# TTL_TO_RS485.net
KiCad netlist of a schematic drawn in Altium Designer
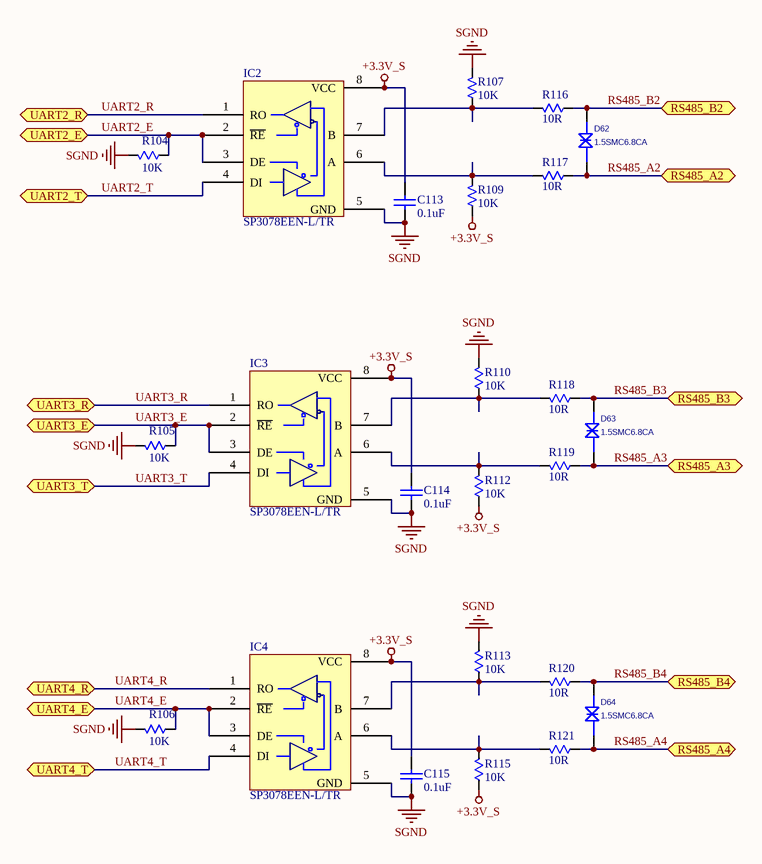
[diagram p0: TTL_TO_RS485.SchDoc]

(export (version "E")
  (design (tool "Eeschema 10.0.6"))
  (components
    (comp (ref "C113")
      (value "0.1uF")
      (footprint "C0805")
      (description "CAP")
      (fields (field (name "PUBLISHER") "Altium Limited"))
      (libsource (lib "Passive Components Class") (part "CAP"))
    )
    (comp (ref "C114")
      (value "0.1uF")
      (footprint "C0805")
      (description "CAP")
      (fields (field (name "PUBLISHER") "Altium Limited"))
      (libsource (lib "Passive Components Class") (part "CAP"))
    )
    (comp (ref "C115")
      (value "0.1uF")
      (footprint "C0805")
      (description "CAP")
      (fields (field (name "PUBLISHER") "Altium Limited"))
      (libsource (lib "Passive Components Class") (part "CAP"))
    )
    (comp (ref "D62")
      (value "1.5SMC6.8CA")
      (footprint "SMB")
      (fields (field (name "MANUFACTURER") "SemiTel"))
      (libsource (lib "*") (part "P0080_1"))
    )
    (comp (ref "D63")
      (value "1.5SMC6.8CA")
      (footprint "SMB")
      (fields (field (name "MANUFACTURER") "SemiTel"))
      (libsource (lib "*") (part "P0080_1"))
    )
    (comp (ref "D64")
      (value "1.5SMC6.8CA")
      (footprint "SMB")
      (fields (field (name "MANUFACTURER") "SemiTel"))
      (libsource (lib "*") (part "P0080_1"))
    )
    (comp (ref "IC2")
      (value "SP3078EEN-L/TR")
      (footprint "SO-8")
      (libsource (lib "Interface Class") (part "SP3078EEN"))
    )
    (comp (ref "IC3")
      (value "SP3078EEN-L/TR")
      (footprint "SO-8")
      (libsource (lib "Interface Class") (part "SP3078EEN"))
    )
    (comp (ref "IC4")
      (value "SP3078EEN-L/TR")
      (footprint "SO-8")
      (libsource (lib "Interface Class") (part "SP3078EEN"))
    )
    (comp (ref "R104")
      (value "10K")
      (footprint "R0805")
      (description "Resistor")
      (fields (field (name "PUBLISHER") "Altium Limited"))
      (libsource (lib "Passive Components Class") (part "RES"))
    )
    (comp (ref "R105")
      (value "10K")
      (footprint "R0805")
      (description "Resistor")
      (fields (field (name "PUBLISHER") "Altium Limited"))
      (libsource (lib "Passive Components Class") (part "RES"))
    )
    (comp (ref "R106")
      (value "10K")
      (footprint "R0805")
      (description "Resistor")
      (fields (field (name "PUBLISHER") "Altium Limited"))
      (libsource (lib "Passive Components Class") (part "RES"))
    )
    (comp (ref "R107")
      (value "10K")
      (footprint "R0805")
      (description "Resistor")
      (fields (field (name "PUBLISHER") "Altium Limited"))
      (libsource (lib "") (part "RES_1"))
    )
    (comp (ref "R109")
      (value "10K")
      (footprint "R0805")
      (description "Resistor")
      (fields (field (name "PUBLISHER") "Altium Limited"))
      (libsource (lib "") (part "RES_1"))
    )
    (comp (ref "R110")
      (value "10K")
      (footprint "R0805")
      (description "Resistor")
      (fields (field (name "PUBLISHER") "Altium Limited"))
      (libsource (lib "") (part "RES_1"))
    )
    (comp (ref "R112")
      (value "10K")
      (footprint "R0805")
      (description "Resistor")
      (fields (field (name "PUBLISHER") "Altium Limited"))
      (libsource (lib "") (part "RES_1"))
    )
    (comp (ref "R113")
      (value "10K")
      (footprint "R0805")
      (description "Resistor")
      (fields (field (name "PUBLISHER") "Altium Limited"))
      (libsource (lib "") (part "RES_1"))
    )
    (comp (ref "R115")
      (value "10K")
      (footprint "R0805")
      (description "Resistor")
      (fields (field (name "PUBLISHER") "Altium Limited"))
      (libsource (lib "") (part "RES_1"))
    )
    (comp (ref "R116")
      (value "10R")
      (footprint "R0805")
      (description "Resistor")
      (fields (field (name "PUBLISHER") "Altium Limited"))
      (libsource (lib "Passive Components Class") (part "RES"))
    )
    (comp (ref "R117")
      (value "10R")
      (footprint "R0805")
      (description "Resistor")
      (fields (field (name "PUBLISHER") "Altium Limited"))
      (libsource (lib "Passive Components Class") (part "RES"))
    )
    (comp (ref "R118")
      (value "10R")
      (footprint "R0805")
      (description "Resistor")
      (fields (field (name "PUBLISHER") "Altium Limited"))
      (libsource (lib "Passive Components Class") (part "RES"))
    )
    (comp (ref "R119")
      (value "10R")
      (footprint "R0805")
      (description "Resistor")
      (fields (field (name "PUBLISHER") "Altium Limited"))
      (libsource (lib "Passive Components Class") (part "RES"))
    )
    (comp (ref "R120")
      (value "10R")
      (footprint "R0805")
      (description "Resistor")
      (fields (field (name "PUBLISHER") "Altium Limited"))
      (libsource (lib "Passive Components Class") (part "RES"))
    )
    (comp (ref "R121")
      (value "10R")
      (footprint "R0805")
      (description "Resistor")
      (fields (field (name "PUBLISHER") "Altium Limited"))
      (libsource (lib "Passive Components Class") (part "RES"))
    )
  )
  (nets
    (net (code "1") (name "+3.3V_S") (class "Default")
      (node (ref "C113") (pin "2") (pinfunction "2_2") (pintype "passive"))
      (node (ref "C114") (pin "2") (pinfunction "2_2") (pintype "passive"))
      (node (ref "C115") (pin "2") (pinfunction "2_2") (pintype "passive"))
      (node (ref "IC2") (pin "8") (pinfunction "VCC_8") (pintype "passive"))
      (node (ref "IC3") (pin "8") (pinfunction "VCC_8") (pintype "passive"))
      (node (ref "IC4") (pin "8") (pinfunction "VCC_8") (pintype "passive"))
      (node (ref "R109") (pin "1") (pinfunction "1_1") (pintype "passive"))
      (node (ref "R112") (pin "1") (pinfunction "1_1") (pintype "passive"))
      (node (ref "R115") (pin "1") (pinfunction "1_1") (pintype "passive"))
    )
    (net (code "2") (name "/RS485_A2") (class "Default")
      (node (ref "D62") (pin "2") (pinfunction "2_2") (pintype "passive"))
      (node (ref "R117") (pin "1") (pinfunction "1_1") (pintype "passive"))
    )
    (net (code "3") (name "/RS485_A3") (class "Default")
      (node (ref "D63") (pin "2") (pinfunction "2_2") (pintype "passive"))
      (node (ref "R119") (pin "1") (pinfunction "1_1") (pintype "passive"))
    )
    (net (code "4") (name "/RS485_A4") (class "Default")
      (node (ref "D64") (pin "2") (pinfunction "2_2") (pintype "passive"))
      (node (ref "R121") (pin "1") (pinfunction "1_1") (pintype "passive"))
    )
    (net (code "5") (name "/RS485_B2") (class "Default")
      (node (ref "D62") (pin "1") (pinfunction "1_1") (pintype "passive"))
      (node (ref "R116") (pin "1") (pinfunction "1_1") (pintype "passive"))
    )
    (net (code "6") (name "/RS485_B3") (class "Default")
      (node (ref "D63") (pin "1") (pinfunction "1_1") (pintype "passive"))
      (node (ref "R118") (pin "1") (pinfunction "1_1") (pintype "passive"))
    )
    (net (code "7") (name "/RS485_B4") (class "Default")
      (node (ref "D64") (pin "1") (pinfunction "1_1") (pintype "passive"))
      (node (ref "R120") (pin "1") (pinfunction "1_1") (pintype "passive"))
    )
    (net (code "8") (name "/UART2_E") (class "Default")
      (node (ref "IC2") (pin "2") (pinfunction "~{RE}_2") (pintype "passive"))
      (node (ref "IC2") (pin "3") (pinfunction "DE_3") (pintype "passive"))
      (node (ref "R104") (pin "1") (pinfunction "1_1") (pintype "passive"))
    )
    (net (code "9") (name "/UART2_R") (class "Default")
      (node (ref "IC2") (pin "1") (pinfunction "RO_1") (pintype "passive"))
    )
    (net (code "10") (name "/UART2_T") (class "Default")
      (node (ref "IC2") (pin "4") (pinfunction "DI_4") (pintype "passive"))
    )
    (net (code "11") (name "/UART3_E") (class "Default")
      (node (ref "IC3") (pin "2") (pinfunction "~{RE}_2") (pintype "passive"))
      (node (ref "IC3") (pin "3") (pinfunction "DE_3") (pintype "passive"))
      (node (ref "R105") (pin "1") (pinfunction "1_1") (pintype "passive"))
    )
    (net (code "12") (name "/UART3_R") (class "Default")
      (node (ref "IC3") (pin "1") (pinfunction "RO_1") (pintype "passive"))
    )
    (net (code "13") (name "/UART3_T") (class "Default")
      (node (ref "IC3") (pin "4") (pinfunction "DI_4") (pintype "passive"))
    )
    (net (code "14") (name "/UART4_E") (class "Default")
      (node (ref "IC4") (pin "2") (pinfunction "~{RE}_2") (pintype "passive"))
      (node (ref "IC4") (pin "3") (pinfunction "DE_3") (pintype "passive"))
      (node (ref "R106") (pin "1") (pinfunction "1_1") (pintype "passive"))
    )
    (net (code "15") (name "/UART4_R") (class "Default")
      (node (ref "IC4") (pin "1") (pinfunction "RO_1") (pintype "passive"))
    )
    (net (code "16") (name "/UART4_T") (class "Default")
      (node (ref "IC4") (pin "4") (pinfunction "DI_4") (pintype "passive"))
    )
    (net (code "17") (name "Net-(IC2-A)") (class "Default")
      (node (ref "IC2") (pin "6") (pinfunction "A_6") (pintype "passive"))
      (node (ref "R109") (pin "2") (pinfunction "2_2") (pintype "passive"))
      (node (ref "R117") (pin "2") (pinfunction "2_2") (pintype "passive"))
    )
    (net (code "18") (name "Net-(IC2-B)") (class "Default")
      (node (ref "IC2") (pin "7") (pinfunction "B_7") (pintype "passive"))
      (node (ref "R107") (pin "1") (pinfunction "1_1") (pintype "passive"))
      (node (ref "R116") (pin "2") (pinfunction "2_2") (pintype "passive"))
    )
    (net (code "19") (name "Net-(IC3-A)") (class "Default")
      (node (ref "IC3") (pin "6") (pinfunction "A_6") (pintype "passive"))
      (node (ref "R112") (pin "2") (pinfunction "2_2") (pintype "passive"))
      (node (ref "R119") (pin "2") (pinfunction "2_2") (pintype "passive"))
    )
    (net (code "20") (name "Net-(IC3-B)") (class "Default")
      (node (ref "IC3") (pin "7") (pinfunction "B_7") (pintype "passive"))
      (node (ref "R110") (pin "1") (pinfunction "1_1") (pintype "passive"))
      (node (ref "R118") (pin "2") (pinfunction "2_2") (pintype "passive"))
    )
    (net (code "21") (name "Net-(IC4-A)") (class "Default")
      (node (ref "IC4") (pin "6") (pinfunction "A_6") (pintype "passive"))
      (node (ref "R115") (pin "2") (pinfunction "2_2") (pintype "passive"))
      (node (ref "R121") (pin "2") (pinfunction "2_2") (pintype "passive"))
    )
    (net (code "22") (name "Net-(IC4-B)") (class "Default")
      (node (ref "IC4") (pin "7") (pinfunction "B_7") (pintype "passive"))
      (node (ref "R113") (pin "1") (pinfunction "1_1") (pintype "passive"))
      (node (ref "R120") (pin "2") (pinfunction "2_2") (pintype "passive"))
    )
    (net (code "23") (name "SGND") (class "Default")
      (node (ref "C113") (pin "1") (pinfunction "1_1") (pintype "passive"))
      (node (ref "C114") (pin "1") (pinfunction "1_1") (pintype "passive"))
      (node (ref "C115") (pin "1") (pinfunction "1_1") (pintype "passive"))
      (node (ref "IC2") (pin "5") (pinfunction "GND_5") (pintype "passive"))
      (node (ref "IC3") (pin "5") (pinfunction "GND_5") (pintype "passive"))
      (node (ref "IC4") (pin "5") (pinfunction "GND_5") (pintype "passive"))
      (node (ref "R104") (pin "2") (pinfunction "2_2") (pintype "passive"))
      (node (ref "R105") (pin "2") (pinfunction "2_2") (pintype "passive"))
      (node (ref "R106") (pin "2") (pinfunction "2_2") (pintype "passive"))
      (node (ref "R107") (pin "2") (pinfunction "2_2") (pintype "passive"))
      (node (ref "R110") (pin "2") (pinfunction "2_2") (pintype "passive"))
      (node (ref "R113") (pin "2") (pinfunction "2_2") (pintype "passive"))
    )
  )
)
